# MAZE_IR.net
KiCad netlist of a schematic drawn in EAGLE
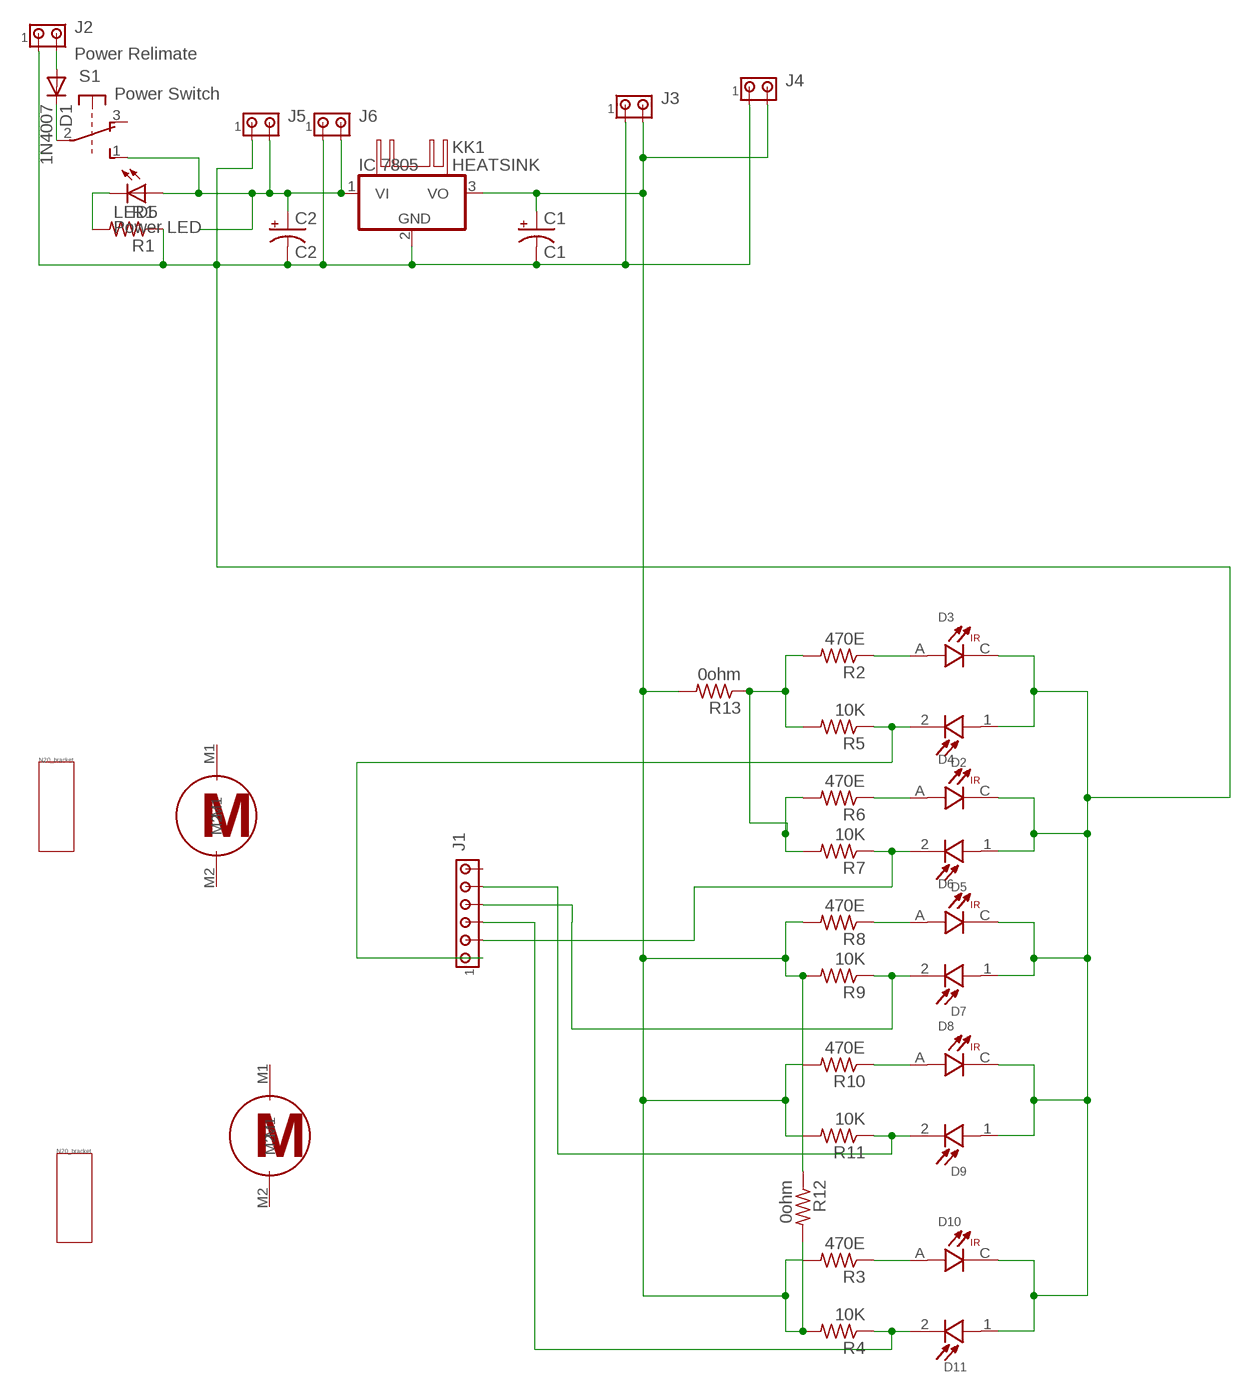
[diagram p0: schematic, sheet 1]

(export (version "E")
  (design (tool "Eeschema 10.0.6"))
  (components
    (comp (ref "C1")
      (value "C1")
      (footprint "eagle-import:CPOL-RADIAL-5MM-10MM")
      (libsource (lib "eagle-import") (part "1000UF-RADIAL-5MM-25V-20%"))
    )
    (comp (ref "C2")
      (value "C2")
      (footprint "eagle-import:E3,5-8")
      (libsource (lib "eagle-import") (part "CPOL-USE3.5-8"))
    )
    (comp (ref "D1")
      (value "1N4007")
      (footprint "eagle-import:DO41-10")
      (libsource (lib "eagle-import") (part "1N4004"))
    )
    (comp (ref "D2")
      (value "SFH_213_FA")
      (footprint "eagle-import:XDCR_SFH_213_FA")
      (fields (field (name "MF") "OSRAM Opto") (field (name "MP") "SFH 213 FA"))
      (libsource (lib "eagle-import") (part "SFH_213_FA"))
    )
    (comp (ref "D3")
      (value "TSHG8200")
      (footprint "eagle-import:LEDRD254W55D595H900")
      (fields (field (name "MF") "Vishay Semiconductor"))
      (libsource (lib "eagle-import") (part "TSHG8200"))
    )
    (comp (ref "D4")
      (value "TSHG8200")
      (footprint "eagle-import:LEDRD254W55D595H900")
      (fields (field (name "MF") "Vishay Semiconductor"))
      (libsource (lib "eagle-import") (part "TSHG8200"))
    )
    (comp (ref "D5")
      (value "SFH_213_FA")
      (footprint "eagle-import:XDCR_SFH_213_FA")
      (fields (field (name "MF") "OSRAM Opto") (field (name "MP") "SFH 213 FA"))
      (libsource (lib "eagle-import") (part "SFH_213_FA"))
    )
    (comp (ref "D6")
      (value "TSHG8200")
      (footprint "eagle-import:LEDRD254W55D595H900")
      (fields (field (name "MF") "Vishay Semiconductor"))
      (libsource (lib "eagle-import") (part "TSHG8200"))
    )
    (comp (ref "D7")
      (value "SFH_213_FA")
      (footprint "eagle-import:XDCR_SFH_213_FA")
      (fields (field (name "MF") "OSRAM Opto") (field (name "MP") "SFH 213 FA"))
      (libsource (lib "eagle-import") (part "SFH_213_FA"))
    )
    (comp (ref "D8")
      (value "TSHG8200")
      (footprint "eagle-import:LEDRD254W55D595H900")
      (fields (field (name "MF") "Vishay Semiconductor"))
      (libsource (lib "eagle-import") (part "TSHG8200"))
    )
    (comp (ref "D9")
      (value "SFH_213_FA")
      (footprint "eagle-import:XDCR_SFH_213_FA")
      (fields (field (name "MF") "OSRAM Opto") (field (name "MP") "SFH 213 FA"))
      (libsource (lib "eagle-import") (part "SFH_213_FA"))
    )
    (comp (ref "D10")
      (value "TSHG8200")
      (footprint "eagle-import:LEDRD254W55D595H900")
      (fields (field (name "MF") "Vishay Semiconductor"))
      (libsource (lib "eagle-import") (part "TSHG8200"))
    )
    (comp (ref "D11")
      (value "SFH_213_FA")
      (footprint "eagle-import:XDCR_SFH_213_FA")
      (fields (field (name "MF") "OSRAM Opto") (field (name "MP") "SFH 213 FA"))
      (libsource (lib "eagle-import") (part "SFH_213_FA"))
    )
    (comp (ref "IC3")
      (value "IC 7805")
      (footprint "eagle-import:TO220V")
      (libsource (lib "eagle-import") (part "78TV05"))
    )
    (comp (ref "J1")
      (value "Line Tracer Relimate")
      (footprint "eagle-import:10X06MTA")
      (libsource (lib "eagle-import") (part "MTA06-100"))
    )
    (comp (ref "J2")
      (value "Power Relimate")
      (footprint "eagle-import:10X02MTA")
      (libsource (lib "eagle-import") (part "MTA02-100"))
    )
    (comp (ref "J3")
      (value "Power Relimate")
      (footprint "eagle-import:10X02MTA")
      (libsource (lib "eagle-import") (part "MTA02-100"))
    )
    (comp (ref "J4")
      (value "Power Relimate")
      (footprint "eagle-import:10X02MTA")
      (libsource (lib "eagle-import") (part "MTA02-100"))
    )
    (comp (ref "J5")
      (value "Power Relimate")
      (footprint "eagle-import:10X02MTA")
      (libsource (lib "eagle-import") (part "MTA02-100"))
    )
    (comp (ref "J6")
      (value "Power Relimate")
      (footprint "eagle-import:10X02MTA")
      (libsource (lib "eagle-import") (part "MTA02-100"))
    )
    (comp (ref "KK1")
      (value "HEATSINK")
      (footprint "eagle-import:HEATSINK")
      (libsource (lib "eagle-import") (part "HEATSINK"))
    )
    (comp (ref "LED5")
      (value "Power LED")
      (footprint "eagle-import:LED3MM")
      (libsource (lib "eagle-import") (part "LED3MM"))
    )
    (comp (ref "R1")
      (value "R1")
      (footprint "eagle-import:0204_7")
      (libsource (lib "eagle-import") (part "R-US_0204/7"))
    )
    (comp (ref "R2")
      (value "470E")
      (footprint "eagle-import:0204_7")
      (libsource (lib "eagle-import") (part "R-US_0204/7"))
    )
    (comp (ref "R3")
      (value "470E")
      (footprint "eagle-import:0204_7")
      (libsource (lib "eagle-import") (part "R-US_0204/7"))
    )
    (comp (ref "R4")
      (value "10K")
      (footprint "eagle-import:0204_7")
      (libsource (lib "eagle-import") (part "R-US_0204/7"))
    )
    (comp (ref "R5")
      (value "10K")
      (footprint "eagle-import:0204_7")
      (libsource (lib "eagle-import") (part "R-US_0204/7"))
    )
    (comp (ref "R6")
      (value "470E")
      (footprint "eagle-import:0204_7")
      (libsource (lib "eagle-import") (part "R-US_0204/7"))
    )
    (comp (ref "R7")
      (value "10K")
      (footprint "eagle-import:0204_7")
      (libsource (lib "eagle-import") (part "R-US_0204/7"))
    )
    (comp (ref "R8")
      (value "470E")
      (footprint "eagle-import:0204_7")
      (libsource (lib "eagle-import") (part "R-US_0204/7"))
    )
    (comp (ref "R9")
      (value "10K")
      (footprint "eagle-import:0204_7")
      (libsource (lib "eagle-import") (part "R-US_0204/7"))
    )
    (comp (ref "R10")
      (value "470E")
      (footprint "eagle-import:0204_7")
      (libsource (lib "eagle-import") (part "R-US_0204/7"))
    )
    (comp (ref "R11")
      (value "10K")
      (footprint "eagle-import:0204_7")
      (libsource (lib "eagle-import") (part "R-US_0204/7"))
    )
    (comp (ref "R12")
      (value "0ohm")
      (footprint "eagle-import:0204_7")
      (libsource (lib "eagle-import") (part "R-US_0204/7"))
    )
    (comp (ref "R13")
      (value "0ohm")
      (footprint "eagle-import:0204_7")
      (libsource (lib "eagle-import") (part "R-US_0204/7"))
    )
    (comp (ref "S1")
      (value "Power Switch")
      (footprint "eagle-import:9077-2")
      (libsource (lib "eagle-import") (part "9077-2"))
    )
    (comp (ref "U$1")
      (value "MOTOR_N20")
      (footprint "eagle-import:MOTOR_N20")
      (libsource (lib "eagle-import") (part "MOTOR_N20"))
    )
    (comp (ref "U$2")
      (value "MOTOR_N20")
      (footprint "eagle-import:MOTOR_N20")
      (libsource (lib "eagle-import") (part "MOTOR_N20"))
    )
    (comp (ref "U$4")
      (value "N20_BRACKET")
      (footprint "eagle-import:BRACKER")
      (libsource (lib "eagle-import") (part "N20_BRACKET"))
    )
    (comp (ref "U$5")
      (value "N20_BRACKET")
      (footprint "eagle-import:BRACKER")
      (libsource (lib "eagle-import") (part "N20_BRACKET"))
    )
  )
  (nets
    (net (code "1") (name "/N$45") (class "Default")
      (node (ref "D6") (pin "A") (pinfunction "A_A") (pintype "passive"))
      (node (ref "D8") (pin "A") (pinfunction "A_A") (pintype "passive"))
      (node (ref "R10") (pin "1") (pinfunction "1_1") (pintype "passive"))
      (node (ref "R8") (pin "1") (pinfunction "1_1") (pintype "passive"))
    )
    (net (code "2") (name "Net-(D1-PadA)") (class "Default")
      (node (ref "D1") (pin "A") (pinfunction "A_A") (pintype "passive"))
      (node (ref "J2") (pin "2") (pinfunction "2_2") (pintype "passive"))
    )
    (net (code "3") (name "Net-(D2-C)") (class "Default")
      (node (ref "D2") (pin "2") (pinfunction "C_2") (pintype "passive"))
      (node (ref "J1") (pin "6") (pinfunction "1_6") (pintype "passive"))
      (node (ref "R5") (pin "1") (pinfunction "1_1") (pintype "passive"))
    )
    (net (code "4") (name "Net-(D3-PadA)") (class "Default")
      (node (ref "D3") (pin "A") (pinfunction "A_A") (pintype "passive"))
      (node (ref "R2") (pin "1") (pinfunction "1_1") (pintype "passive"))
    )
    (net (code "5") (name "Net-(D4-PadA)") (class "Default")
      (node (ref "D4") (pin "A") (pinfunction "A_A") (pintype "passive"))
      (node (ref "R6") (pin "1") (pinfunction "1_1") (pintype "passive"))
    )
    (net (code "6") (name "Net-(D5-C)") (class "Default")
      (node (ref "D5") (pin "2") (pinfunction "C_2") (pintype "passive"))
      (node (ref "J1") (pin "5") (pinfunction "2_5") (pintype "passive"))
      (node (ref "R7") (pin "1") (pinfunction "1_1") (pintype "passive"))
    )
    (net (code "7") (name "Net-(D7-C)") (class "Default")
      (node (ref "D7") (pin "2") (pinfunction "C_2") (pintype "passive"))
      (node (ref "J1") (pin "3") (pinfunction "4_3") (pintype "passive"))
      (node (ref "R9") (pin "1") (pinfunction "1_1") (pintype "passive"))
    )
    (net (code "8") (name "Net-(D9-C)") (class "Default")
      (node (ref "D9") (pin "2") (pinfunction "C_2") (pintype "passive"))
      (node (ref "J1") (pin "2") (pinfunction "5_2") (pintype "passive"))
      (node (ref "R11") (pin "1") (pinfunction "1_1") (pintype "passive"))
    )
    (net (code "9") (name "Net-(D10-PadA)") (class "Default")
      (node (ref "D10") (pin "A") (pinfunction "A_A") (pintype "passive"))
      (node (ref "R3") (pin "1") (pinfunction "1_1") (pintype "passive"))
    )
    (net (code "10") (name "Net-(D11-A)") (class "Default")
      (node (ref "C1") (pin "-") (pinfunction "-_-") (pintype "passive"))
      (node (ref "C2") (pin "-") (pinfunction "-_-") (pintype "passive"))
      (node (ref "D10") (pin "C") (pinfunction "C_C") (pintype "passive"))
      (node (ref "D11") (pin "1") (pinfunction "A_1") (pintype "passive"))
      (node (ref "D2") (pin "1") (pinfunction "A_1") (pintype "passive"))
      (node (ref "D3") (pin "C") (pinfunction "C_C") (pintype "passive"))
      (node (ref "D4") (pin "C") (pinfunction "C_C") (pintype "passive"))
      (node (ref "D5") (pin "1") (pinfunction "A_1") (pintype "passive"))
      (node (ref "D6") (pin "C") (pinfunction "C_C") (pintype "passive"))
      (node (ref "D7") (pin "1") (pinfunction "A_1") (pintype "passive"))
      (node (ref "D8") (pin "C") (pinfunction "C_C") (pintype "passive"))
      (node (ref "D9") (pin "1") (pinfunction "A_1") (pintype "passive"))
      (node (ref "IC3") (pin "2") (pinfunction "GND_2") (pintype "passive"))
      (node (ref "J2") (pin "1") (pinfunction "1_1") (pintype "passive"))
      (node (ref "J3") (pin "1") (pinfunction "1_1") (pintype "passive"))
      (node (ref "J4") (pin "1") (pinfunction "1_1") (pintype "passive"))
      (node (ref "J5") (pin "1") (pinfunction "1_1") (pintype "passive"))
      (node (ref "J6") (pin "1") (pinfunction "1_1") (pintype "passive"))
      (node (ref "R1") (pin "1") (pinfunction "1_1") (pintype "passive"))
    )
    (net (code "11") (name "Net-(D11-C)") (class "Default")
      (node (ref "D11") (pin "2") (pinfunction "C_2") (pintype "passive"))
      (node (ref "J1") (pin "4") (pinfunction "3_4") (pintype "passive"))
      (node (ref "R4") (pin "1") (pinfunction "1_1") (pintype "passive"))
    )
    (net (code "12") (name "Net-(IC3-VI)") (class "Default")
      (node (ref "C2") (pin "+") (pinfunction "+_+") (pintype "passive"))
      (node (ref "IC3") (pin "1") (pinfunction "VI_1") (pintype "input"))
      (node (ref "J5") (pin "2") (pinfunction "2_2") (pintype "passive"))
      (node (ref "J6") (pin "2") (pinfunction "2_2") (pintype "passive"))
      (node (ref "LED5") (pin "A") (pinfunction "A_A") (pintype "passive"))
      (node (ref "S1") (pin "1") (pinfunction "S_1") (pintype "passive"))
    )
    (net (code "13") (name "Net-(IC3-VO)") (class "Default")
      (node (ref "C1") (pin "+") (pinfunction "+_+") (pintype "passive"))
      (node (ref "IC3") (pin "3") (pinfunction "VO_3") (pintype "passive"))
      (node (ref "J3") (pin "2") (pinfunction "2_2") (pintype "passive"))
      (node (ref "J4") (pin "2") (pinfunction "2_2") (pintype "passive"))
      (node (ref "R10") (pin "2") (pinfunction "2_2") (pintype "passive"))
      (node (ref "R11") (pin "2") (pinfunction "2_2") (pintype "passive"))
      (node (ref "R12") (pin "1") (pinfunction "1_1") (pintype "passive"))
      (node (ref "R12") (pin "2") (pinfunction "2_2") (pintype "passive"))
      (node (ref "R13") (pin "2") (pinfunction "2_2") (pintype "passive"))
      (node (ref "R3") (pin "2") (pinfunction "2_2") (pintype "passive"))
      (node (ref "R4") (pin "2") (pinfunction "2_2") (pintype "passive"))
      (node (ref "R8") (pin "2") (pinfunction "2_2") (pintype "passive"))
      (node (ref "R9") (pin "2") (pinfunction "2_2") (pintype "passive"))
    )
    (net (code "14") (name "Net-(LED5-C)") (class "Default")
      (node (ref "LED5") (pin "K") (pinfunction "C_K") (pintype "passive"))
      (node (ref "R1") (pin "2") (pinfunction "2_2") (pintype "passive"))
    )
    (net (code "15") (name "Net-(R13-Pad1)") (class "Default")
      (node (ref "R13") (pin "1") (pinfunction "1_1") (pintype "passive"))
      (node (ref "R2") (pin "2") (pinfunction "2_2") (pintype "passive"))
      (node (ref "R5") (pin "2") (pinfunction "2_2") (pintype "passive"))
      (node (ref "R6") (pin "2") (pinfunction "2_2") (pintype "passive"))
      (node (ref "R7") (pin "2") (pinfunction "2_2") (pintype "passive"))
    )
    (net (code "16") (name "Net-(S1A-P)") (class "Default")
      (node (ref "D1") (pin "C") (pinfunction "C_C") (pintype "passive"))
      (node (ref "S1") (pin "2") (pinfunction "P_2") (pintype "passive"))
    )
    (net (code "17") (name "unconnected-(J1-6-Pad1)") (class "Default")
      (node (ref "J1") (pin "1") (pinfunction "6_1") (pintype "passive"))
    )
    (net (code "18") (name "unconnected-(S1A-O-Pad3)") (class "Default")
      (node (ref "S1") (pin "3") (pinfunction "O_3") (pintype "passive"))
    )
    (net (code "19") (name "unconnected-(U$1-PadM1)") (class "Default")
      (node (ref "U$1") (pin "M1") (pinfunction "M1_M1") (pintype "bidirectional"))
    )
    (net (code "20") (name "unconnected-(U$1-PadM2)") (class "Default")
      (node (ref "U$1") (pin "M2") (pinfunction "M2_M2") (pintype "bidirectional"))
    )
    (net (code "21") (name "unconnected-(U$2-PadM1)") (class "Default")
      (node (ref "U$2") (pin "M1") (pinfunction "M1_M1") (pintype "bidirectional"))
    )
    (net (code "22") (name "unconnected-(U$2-PadM2)") (class "Default")
      (node (ref "U$2") (pin "M2") (pinfunction "M2_M2") (pintype "bidirectional"))
    )
  )
)
